# harp_behavior_encoder_v1_0.net
KiCad netlist of a schematic drawn in EAGLE
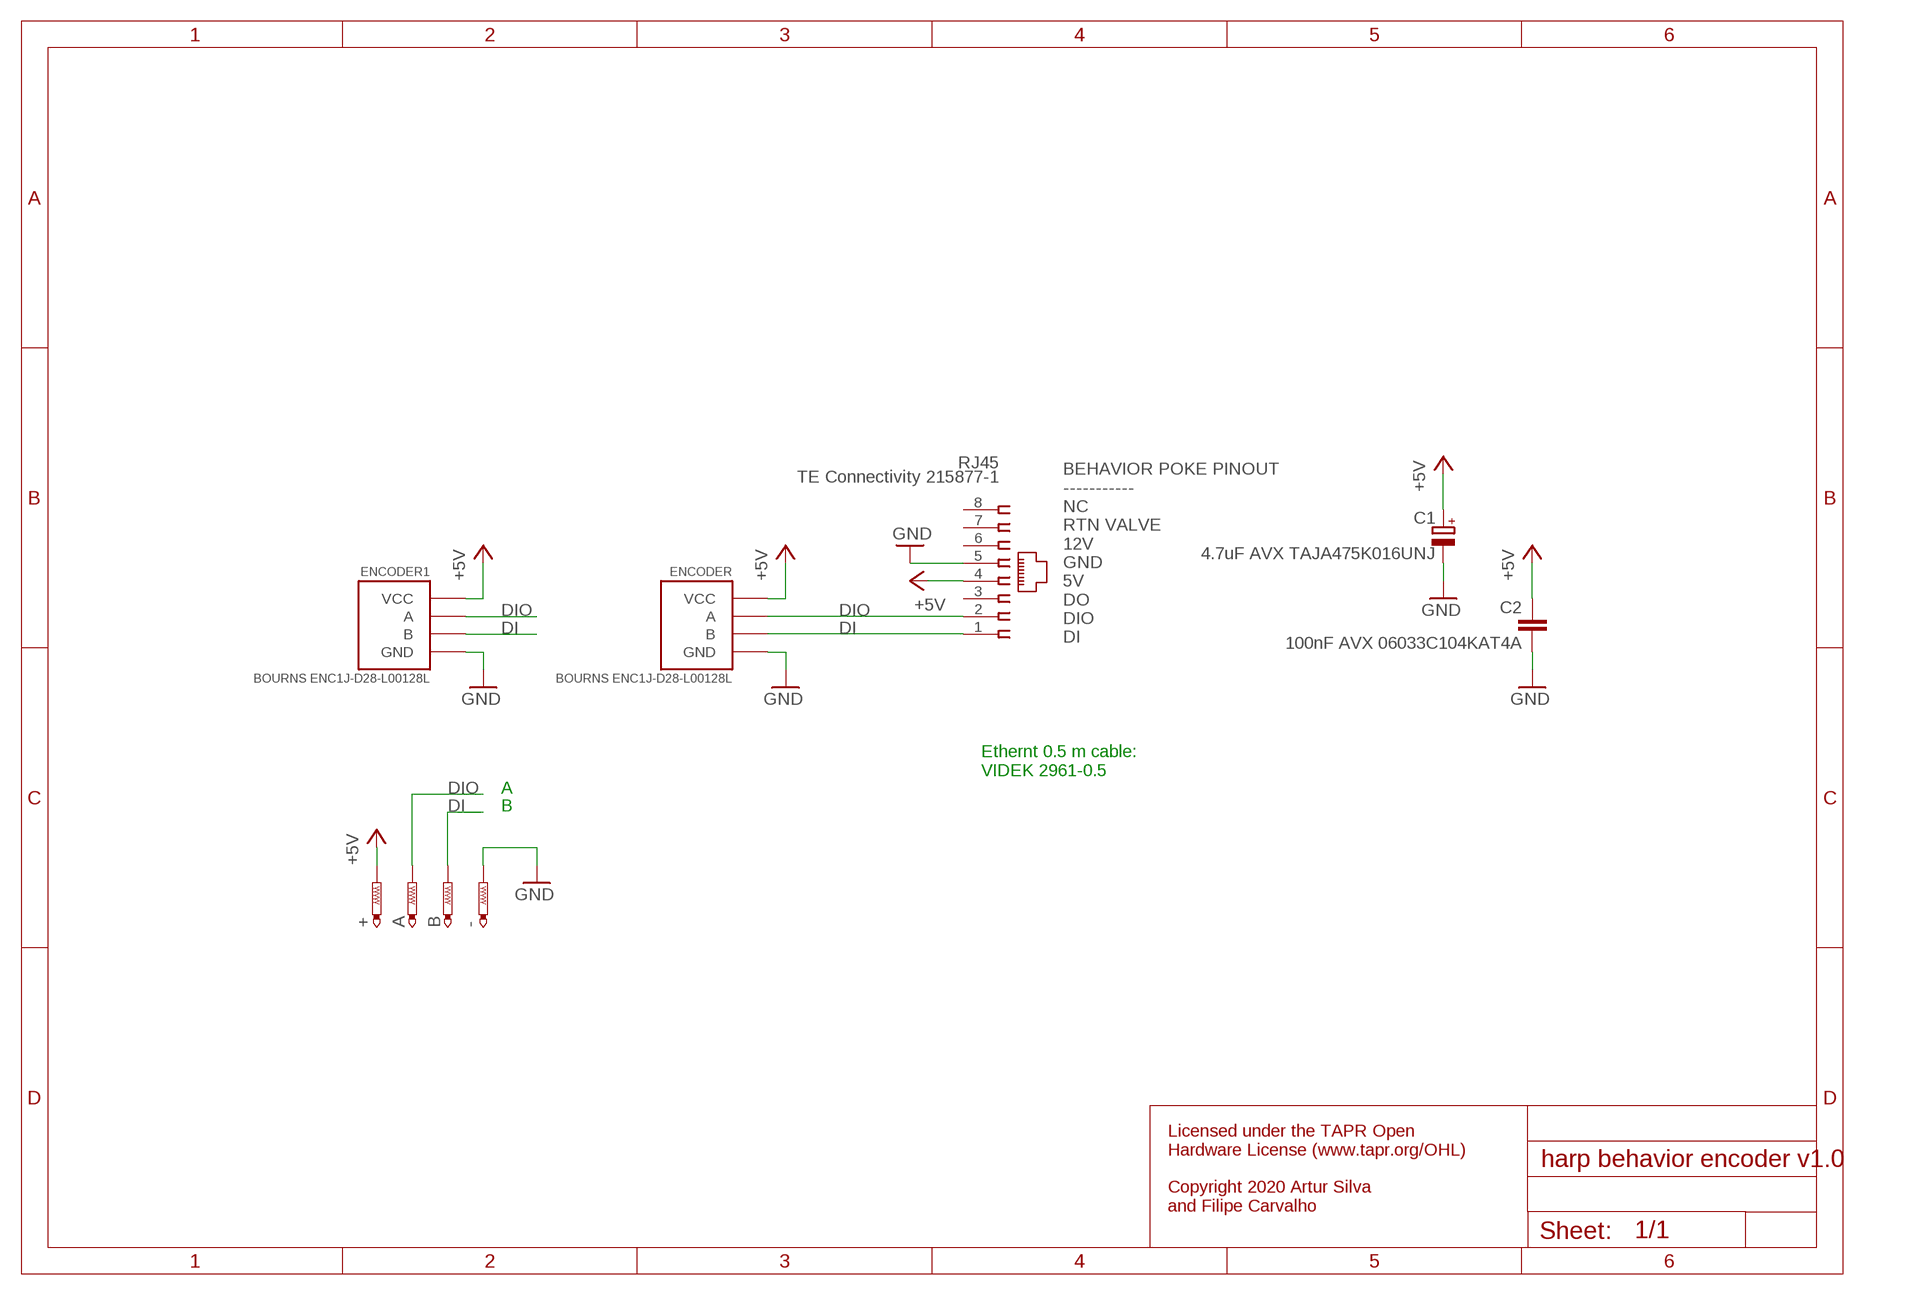
[diagram p0: schematic, sheet 1]

(export (version "E")
  (design (tool "Eeschema 10.0.6"))
  (components
    (comp (ref "+")
      (value "PTR1PAD1-13")
      (footprint "eagle-import:P1-13")
      (libsource (lib "eagle-import") (part "PTR1PAD1-13"))
    )
    (comp (ref "-")
      (value "PTR1PAD1-13")
      (footprint "eagle-import:P1-13")
      (libsource (lib "eagle-import") (part "PTR1PAD1-13"))
    )
    (comp (ref "A")
      (value "PTR1PAD1-13")
      (footprint "eagle-import:P1-13")
      (libsource (lib "eagle-import") (part "PTR1PAD1-13"))
    )
    (comp (ref "B")
      (value "PTR1PAD1-13")
      (footprint "eagle-import:P1-13")
      (libsource (lib "eagle-import") (part "PTR1PAD1-13"))
    )
    (comp (ref "C1")
      (value "4.7uF AVX TAJA475K016UNJ")
      (footprint "eagle-import:A_3216-18W")
      (libsource (lib "eagle-import") (part "CPOL-EUA/3216-18W"))
    )
    (comp (ref "C2")
      (value "100nF AVX 06033C104KAT4A")
      (footprint "eagle-import:C0603")
      (libsource (lib "eagle-import") (part "C-EUC0603"))
    )
    (comp (ref "ENCODER")
      (value "BOURNS ENC1J-D28-L00128L")
      (footprint "eagle-import:STYLEC")
      (libsource (lib "eagle-import") (part "BOURNS_EN"))
    )
    (comp (ref "ENCODER1")
      (value "BOURNS ENC1J-D28-L00128L")
      (footprint "eagle-import:STYLEC")
      (libsource (lib "eagle-import") (part "BOURNS_EN"))
    )
    (comp (ref "RJ45")
      (value "TE Connectivity 215877-1")
      (footprint "eagle-import:520426-4")
      (libsource (lib "eagle-import") (part "520426-4"))
    )
  )
  (nets
    (net (code "1") (name "+5V") (class "Default")
      (node (ref "+") (pin "TP") (pinfunction "TP_TP") (pintype "input"))
      (node (ref "C1") (pin "+") (pinfunction "+_+") (pintype "passive"))
      (node (ref "C2") (pin "1") (pinfunction "1_1") (pintype "passive"))
      (node (ref "ENCODER") (pin "+") (pinfunction "VCC_+") (pintype "bidirectional"))
      (node (ref "ENCODER1") (pin "+") (pinfunction "VCC_+") (pintype "bidirectional"))
      (node (ref "RJ45") (pin "4") (pinfunction "4_4") (pintype "passive"))
    )
    (net (code "2") (name "/DI") (class "Default")
      (node (ref "B") (pin "TP") (pinfunction "TP_TP") (pintype "input"))
      (node (ref "ENCODER") (pin "B") (pinfunction "B_B") (pintype "bidirectional"))
      (node (ref "ENCODER1") (pin "B") (pinfunction "B_B") (pintype "bidirectional"))
      (node (ref "RJ45") (pin "1") (pinfunction "1_1") (pintype "passive"))
    )
    (net (code "3") (name "/DIO") (class "Default")
      (node (ref "A") (pin "TP") (pinfunction "TP_TP") (pintype "input"))
      (node (ref "ENCODER") (pin "A") (pinfunction "A_A") (pintype "bidirectional"))
      (node (ref "ENCODER1") (pin "A") (pinfunction "A_A") (pintype "bidirectional"))
      (node (ref "RJ45") (pin "2") (pinfunction "2_2") (pintype "passive"))
    )
    (net (code "4") (name "GND") (class "Default")
      (node (ref "-") (pin "TP") (pinfunction "TP_TP") (pintype "input"))
      (node (ref "C1") (pin "-") (pinfunction "-_-") (pintype "passive"))
      (node (ref "C2") (pin "2") (pinfunction "2_2") (pintype "passive"))
      (node (ref "ENCODER") (pin "-") (pinfunction "GND_-") (pintype "bidirectional"))
      (node (ref "ENCODER1") (pin "-") (pinfunction "GND_-") (pintype "bidirectional"))
      (node (ref "RJ45") (pin "5") (pinfunction "5_5") (pintype "passive"))
    )
    (net (code "5") (name "unconnected-(RJ45-Pad3)") (class "Default")
      (node (ref "RJ45") (pin "3") (pinfunction "3_3") (pintype "passive"))
    )
    (net (code "6") (name "unconnected-(RJ45-Pad6)") (class "Default")
      (node (ref "RJ45") (pin "6") (pinfunction "6_6") (pintype "passive"))
    )
    (net (code "7") (name "unconnected-(RJ45-Pad7)") (class "Default")
      (node (ref "RJ45") (pin "7") (pinfunction "7_7") (pintype "passive"))
    )
    (net (code "8") (name "unconnected-(RJ45-Pad8)") (class "Default")
      (node (ref "RJ45") (pin "8") (pinfunction "8_8") (pintype "passive"))
    )
  )
)
